# PMOS_Load_Switch.net
KiCad netlist of a schematic drawn in Altium Designer
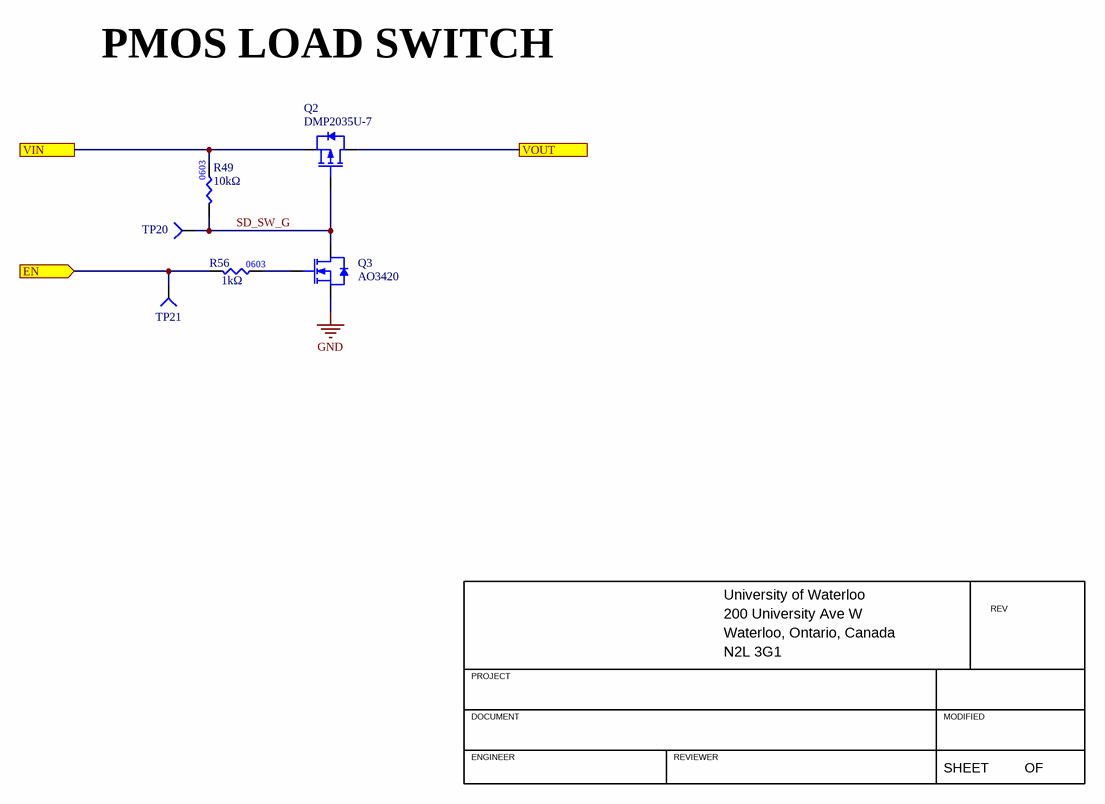
[diagram p0: PMOS Load Switch.SchDoc]

(export (version "E")
  (design (tool "Eeschema 10.0.6"))
  (components
    (comp (ref "Q2")
      (value "PMOS_20V_3.6A")
      (footprint "DIO-INC_SOT23")
      (description "MOSFET P-CH 20V 3.6A SOT23-3")
      (fields (field (name "MANUFACTURER PART NUMBER 1") "DMP2035U-7"))
      (libsource (lib "Personal_Schematic_Library_2022") (part "PMOS_20V_3.6A"))
    )
    (comp (ref "Q3")
      (value "NMOS_20V_6A")
      (footprint "SOT23-3")
      (description "MOSFET N-CH 20V 6A SOT-23")
      (fields (field (name "MANUFACTURER PART NUMBER 1") "AO3420"))
      (libsource (lib "Personal_Schematic_Library_2022") (part "NMOS_20V_6A"))
    )
    (comp (ref "R49")
      (value "10kΩ")
      (footprint "RES0603")
      (description "RES 10K OHM 1% 1/8W 0603")
      (fields (field (name "Comment") "RES_10kΩ_0603_1%"))
      (libsource (lib "Personal_Schematic_Library_2022") (part "RES_10kΩ_0603_1%"))
    )
    (comp (ref "R56")
      (value "1kΩ")
      (footprint "RES0603")
      (description "RES 1K OHM 1% 1/8W 0603")
      (fields (field (name "Comment") "RES_1kΩ_0603_1%"))
      (libsource (lib "Personal_Schematic_Library_2022") (part "RES_1kΩ_0603_1%"))
    )
    (comp (ref "TP20")
      (value "TESTPOINT_1MM_CIRCLE")
      (footprint "TESTPOINT_CIRCLE_1MM")
      (description "TESTPOINT 1MM CIRCLE")
      (libsource (lib "Personal_Schematic_Library_2022") (part "TESTPOINT_1MM_CIRCLE"))
    )
    (comp (ref "TP21")
      (value "TESTPOINT_1MM_CIRCLE")
      (footprint "TESTPOINT_CIRCLE_1MM")
      (description "TESTPOINT 1MM CIRCLE")
      (libsource (lib "Personal_Schematic_Library_2022") (part "TESTPOINT_1MM_CIRCLE"))
    )
  )
  (nets
    (net (code "1") (name "/EN") (class "Default")
      (node (ref "R56") (pin "1") (pinfunction "1_1") (pintype "passive"))
      (node (ref "TP21") (pin "1") (pinfunction "=value_1") (pintype "passive"))
    )
    (net (code "2") (name "/SD_SW_G") (class "Default")
      (node (ref "Q2") (pin "1") (pinfunction "Gate_1") (pintype "passive"))
      (node (ref "Q3") (pin "3") (pinfunction "DRAIN_3") (pintype "passive"))
      (node (ref "R49") (pin "1") (pinfunction "1_1") (pintype "passive"))
      (node (ref "TP20") (pin "1") (pinfunction "=value_1") (pintype "passive"))
    )
    (net (code "3") (name "/VIN") (class "Default")
      (node (ref "Q2") (pin "2") (pinfunction "Source_2") (pintype "passive"))
      (node (ref "R49") (pin "2") (pinfunction "2_2") (pintype "passive"))
    )
    (net (code "4") (name "/VOUT") (class "Default")
      (node (ref "Q2") (pin "3") (pinfunction "Drain_3") (pintype "passive"))
    )
    (net (code "5") (name "GND") (class "Default")
      (node (ref "Q3") (pin "2") (pinfunction "SOURCE_2") (pintype "passive"))
    )
    (net (code "6") (name "Net-(Q3-GATE)") (class "Default")
      (node (ref "Q3") (pin "1") (pinfunction "GATE_1") (pintype "passive"))
      (node (ref "R56") (pin "2") (pinfunction "2_2") (pintype "passive"))
    )
  )
)
